# gameboy-macro.net
KiCad netlist of a schematic drawn in EAGLE
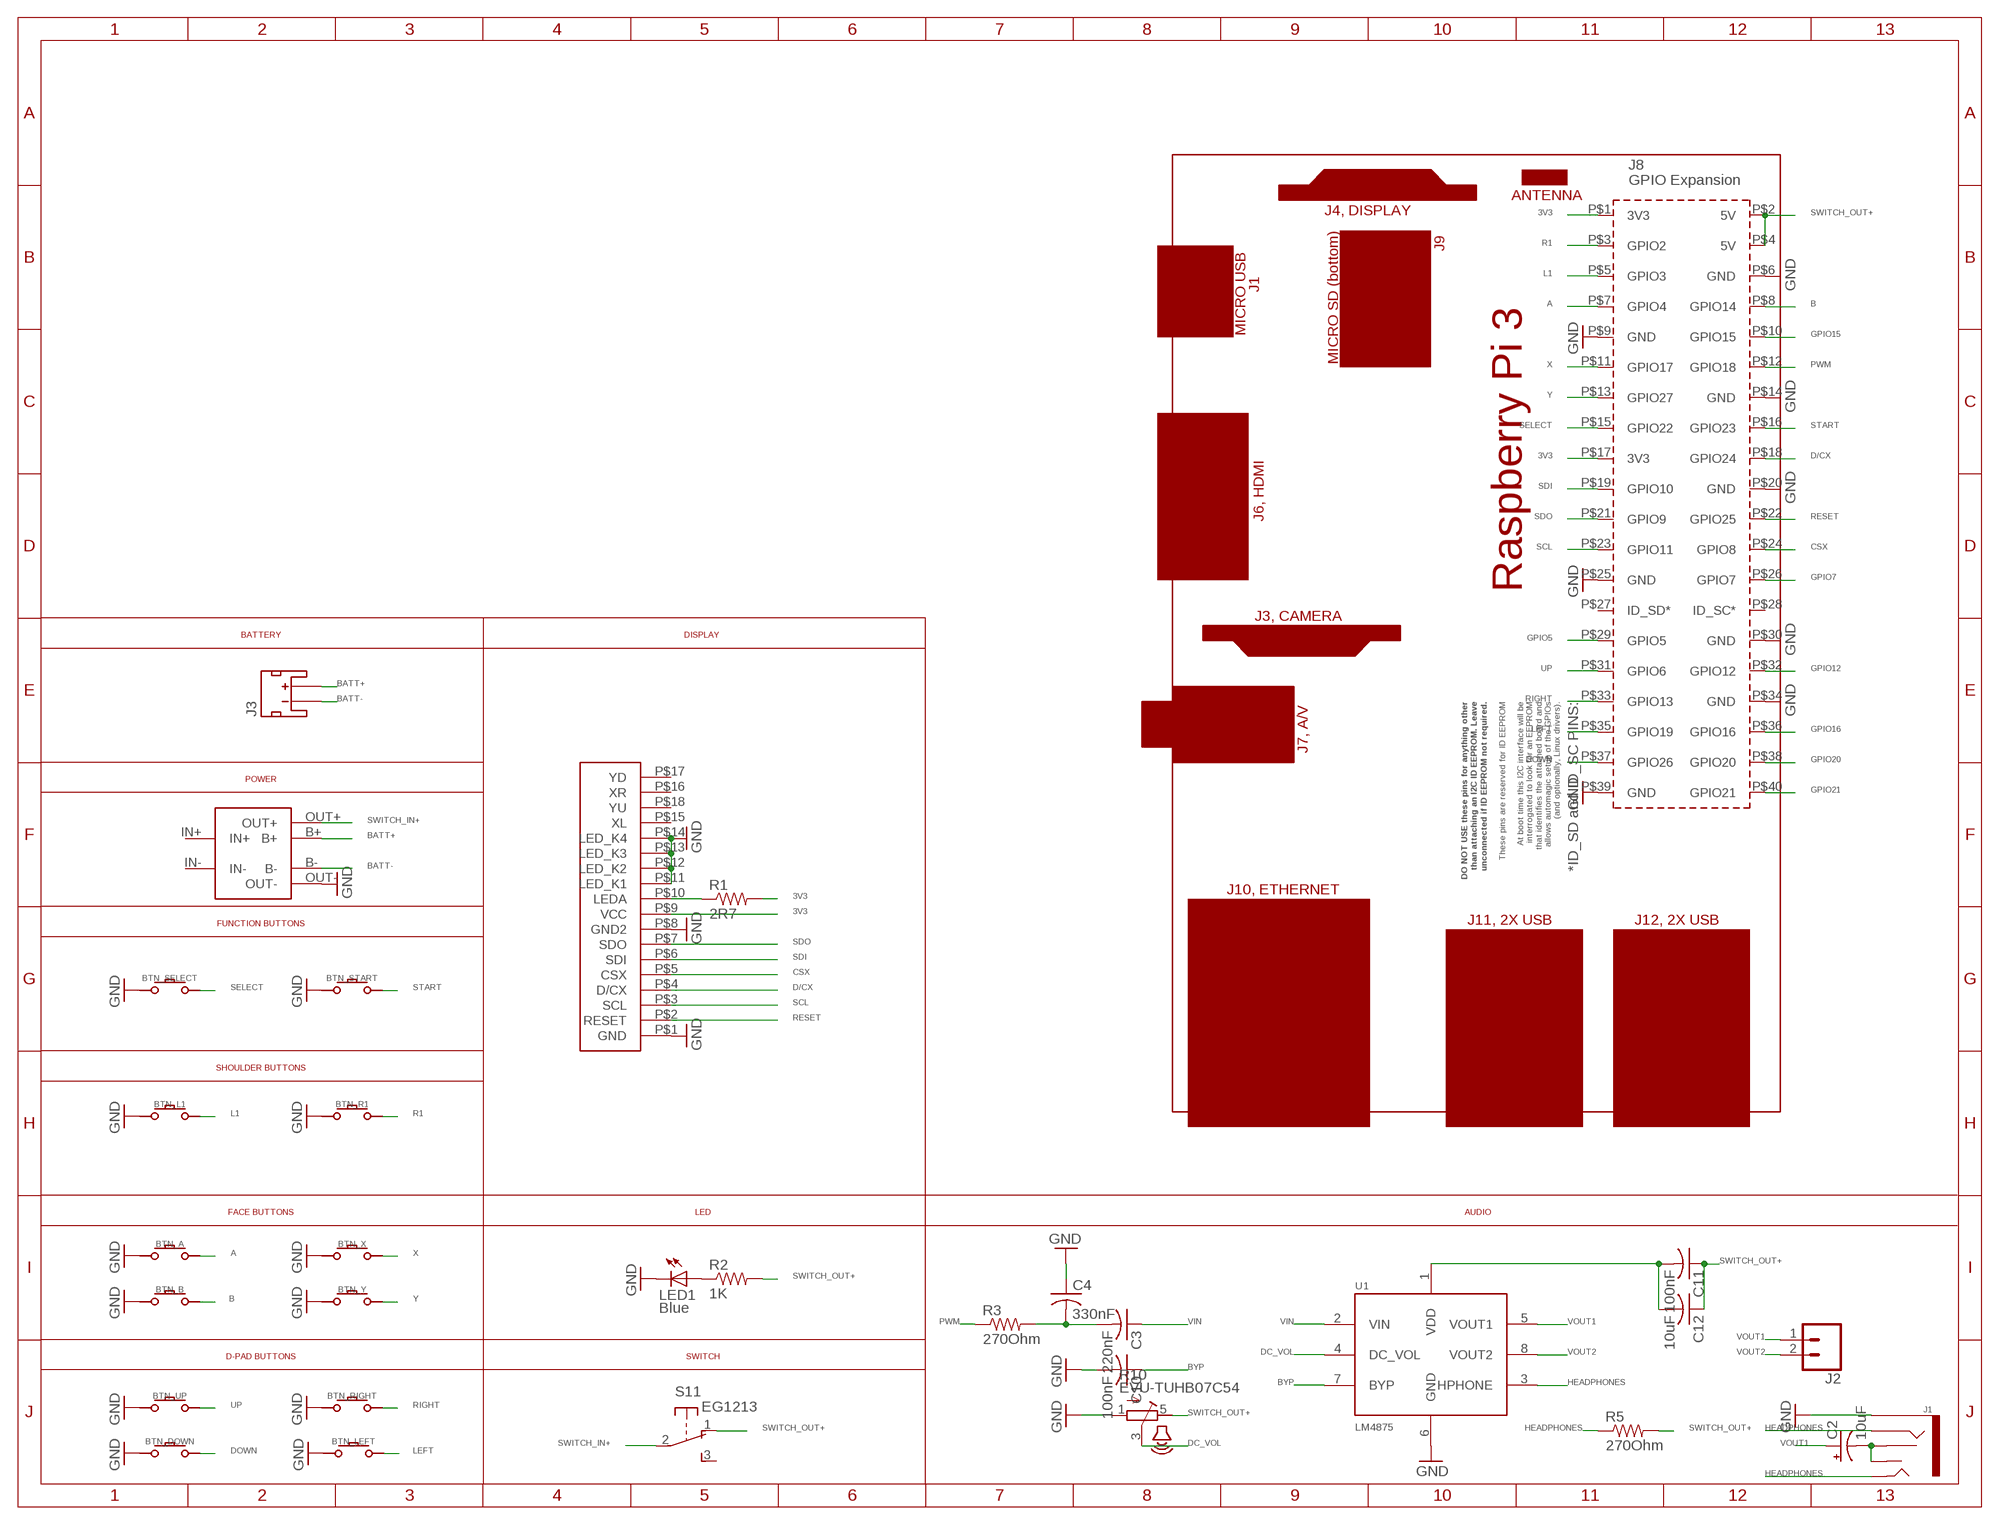
[diagram p0: schematic, sheet 1]

(export (version "E")
  (design (tool "Eeschema 10.0.6"))
  (components
    (comp (ref "BTN_A")
      (value "GAMEBOY-ZERO-BUTTON")
      (footprint "eagle-import:GAMEBOY-ZERO-BUTTON")
      (libsource (lib "eagle-import") (part "GAMEBOY-ZERO-BUTTON"))
    )
    (comp (ref "BTN_B")
      (value "GAMEBOY-ZERO-BUTTON")
      (footprint "eagle-import:GAMEBOY-ZERO-BUTTON")
      (libsource (lib "eagle-import") (part "GAMEBOY-ZERO-BUTTON"))
    )
    (comp (ref "BTN_DOWN")
      (value "GAMEBOY-ZERO-BUTTON")
      (footprint "eagle-import:GAMEBOY-ZERO-BUTTON")
      (libsource (lib "eagle-import") (part "GAMEBOY-ZERO-BUTTON"))
    )
    (comp (ref "BTN_L1")
      (value "GAMEBOY-ZERO-BUTTON")
      (footprint "eagle-import:GAMEBOY-ZERO-BUTTON")
      (libsource (lib "eagle-import") (part "GAMEBOY-ZERO-BUTTON"))
    )
    (comp (ref "BTN_LEFT")
      (value "GAMEBOY-ZERO-BUTTON")
      (footprint "eagle-import:GAMEBOY-ZERO-BUTTON")
      (libsource (lib "eagle-import") (part "GAMEBOY-ZERO-BUTTON"))
    )
    (comp (ref "BTN_R1")
      (value "GAMEBOY-ZERO-BUTTON")
      (footprint "eagle-import:GAMEBOY-ZERO-BUTTON")
      (libsource (lib "eagle-import") (part "GAMEBOY-ZERO-BUTTON"))
    )
    (comp (ref "BTN_RIGHT")
      (value "GAMEBOY-ZERO-BUTTON")
      (footprint "eagle-import:GAMEBOY-ZERO-BUTTON")
      (libsource (lib "eagle-import") (part "GAMEBOY-ZERO-BUTTON"))
    )
    (comp (ref "BTN_SELECT")
      (value "GAMEBOY-ZERO-BUTTON")
      (footprint "eagle-import:GAMEBOY-ZERO-BUTTON")
      (libsource (lib "eagle-import") (part "GAMEBOY-ZERO-BUTTON"))
    )
    (comp (ref "BTN_START")
      (value "GAMEBOY-ZERO-BUTTON")
      (footprint "eagle-import:GAMEBOY-ZERO-BUTTON")
      (libsource (lib "eagle-import") (part "GAMEBOY-ZERO-BUTTON"))
    )
    (comp (ref "BTN_UP")
      (value "GAMEBOY-ZERO-BUTTON")
      (footprint "eagle-import:GAMEBOY-ZERO-BUTTON")
      (libsource (lib "eagle-import") (part "GAMEBOY-ZERO-BUTTON"))
    )
    (comp (ref "BTN_X")
      (value "GAMEBOY-ZERO-BUTTON")
      (footprint "eagle-import:GAMEBOY-ZERO-BUTTON")
      (libsource (lib "eagle-import") (part "GAMEBOY-ZERO-BUTTON"))
    )
    (comp (ref "BTN_Y")
      (value "GAMEBOY-ZERO-BUTTON")
      (footprint "eagle-import:GAMEBOY-ZERO-BUTTON")
      (libsource (lib "eagle-import") (part "GAMEBOY-ZERO-BUTTON"))
    )
    (comp (ref "C2")
      (value "10uF")
      (footprint "eagle-import:EIA3216")
      (libsource (lib "eagle-import") (part "10UF-POLAR-EIA3216-16V-10%(TANT)"))
    )
    (comp (ref "C3")
      (value "220nF")
      (footprint "eagle-import:C0805")
      (libsource (lib "eagle-import") (part "C-USC0805"))
    )
    (comp (ref "C4")
      (value "330nF")
      (footprint "eagle-import:C0805")
      (libsource (lib "eagle-import") (part "C-USC0805"))
    )
    (comp (ref "C10")
      (value "100nF")
      (footprint "eagle-import:C0805")
      (libsource (lib "eagle-import") (part "C-USC0805"))
    )
    (comp (ref "C11")
      (value "100nF")
      (footprint "eagle-import:C0805")
      (libsource (lib "eagle-import") (part "C-USC0805"))
    )
    (comp (ref "C12")
      (value "10uF")
      (footprint "eagle-import:C0805")
      (libsource (lib "eagle-import") (part "C-USC0805"))
    )
    (comp (ref "ILI9341-TFT-2.8")
      (value "GAMEBOYZEROHANDHELDDISPLAYS-3.2")
      (footprint "eagle-import:GAMEBOYZEROHANDHELDDISPLAYS-3.2")
      (libsource (lib "eagle-import") (part "GAMEBOYZEROHANDHELDDISPLAYS-3.2"))
    )
    (comp (ref "J1")
      (value "AUDIO_JACK_3.5MM_PTH")
      (footprint "eagle-import:AUDIO-JACK")
      (libsource (lib "eagle-import") (part "AUDIO_JACK_3.5MM_PTH"))
    )
    (comp (ref "J2")
      (value "CONN_02")
      (footprint "eagle-import:1X02")
      (libsource (lib "eagle-import") (part "CONN_02"))
    )
    (comp (ref "J3")
      (value "JST_2MM_MALE")
      (footprint "eagle-import:JST-2-SMD")
      (libsource (lib "eagle-import") (part "JST_2MM_MALE"))
    )
    (comp (ref "LED1")
      (value "Blue")
      (footprint "eagle-import:CHIPLED_0805")
      (libsource (lib "eagle-import") (part "LEDCHIPLED_0805"))
    )
    (comp (ref "PCB1")
      (value "RPI3RPI3")
      (footprint "eagle-import:RPI3")
      (libsource (lib "eagle-import") (part "RPI3RPI3"))
    )
    (comp (ref "POWER1")
      (value "03962A")
      (footprint "eagle-import:03962A")
      (libsource (lib "eagle-import") (part "03962A"))
    )
    (comp (ref "R1")
      (value "2R7")
      (footprint "eagle-import:R0805")
      (libsource (lib "eagle-import") (part "R-US_R0805"))
    )
    (comp (ref "R2")
      (value "1K")
      (footprint "eagle-import:R0805")
      (libsource (lib "eagle-import") (part "R-US_R0805"))
    )
    (comp (ref "R3")
      (value "270Ohm")
      (footprint "eagle-import:R0805")
      (libsource (lib "eagle-import") (part "adafruit_420_R-US_R0805"))
    )
    (comp (ref "R5")
      (value "270Ohm")
      (footprint "eagle-import:R0805")
      (libsource (lib "eagle-import") (part "adafruit_420_R-US_R0805"))
    )
    (comp (ref "R10")
      (value "EVU-TUHB07C54")
      (footprint "eagle-import:VOLUME")
      (libsource (lib "eagle-import") (part "VOLUME"))
    )
    (comp (ref "S1")
      (value "EG1213")
      (footprint "eagle-import:EG1213")
      (libsource (lib "eagle-import") (part "EG1213"))
    )
    (comp (ref "U1")
      (value "LM4875")
      (footprint "eagle-import:SOIC8")
      (libsource (lib "eagle-import") (part "LM4875"))
    )
  )
  (nets
    (net (code "1") (name "/3V3") (class "Default")
      (node (ref "ILI9341-TFT-2.8") (pin "P$9") (pinfunction "VCC_P$9") (pintype "bidirectional"))
      (node (ref "PCB1") (pin "P$1") (pinfunction "3V3_P$1") (pintype "bidirectional"))
      (node (ref "PCB1") (pin "P$17") (pinfunction "3V3_P$17") (pintype "bidirectional"))
      (node (ref "R1") (pin "2") (pinfunction "2_2") (pintype "passive"))
    )
    (net (code "2") (name "/A") (class "Default")
      (node (ref "BTN_A") (pin "P$ACTIVE") (pinfunction "P$ACTIVE_P$ACTIVE") (pintype "bidirectional"))
      (node (ref "PCB1") (pin "P$7") (pinfunction "GPIO4_P$7") (pintype "bidirectional"))
    )
    (net (code "3") (name "/B") (class "Default")
      (node (ref "BTN_B") (pin "P$ACTIVE") (pinfunction "P$ACTIVE_P$ACTIVE") (pintype "bidirectional"))
      (node (ref "PCB1") (pin "P$8") (pinfunction "GPIO14_P$8") (pintype "bidirectional"))
    )
    (net (code "4") (name "/BATT+") (class "Default")
      (node (ref "J3") (pin "2") (pinfunction "+_2") (pintype "bidirectional"))
      (node (ref "POWER1") (pin "B+") (pinfunction "B+_B+") (pintype "bidirectional"))
    )
    (net (code "5") (name "/BATT-") (class "Default")
      (node (ref "J3") (pin "1") (pinfunction "-_1") (pintype "bidirectional"))
      (node (ref "POWER1") (pin "B-") (pinfunction "B-_B-") (pintype "bidirectional"))
    )
    (net (code "6") (name "/BYP") (class "Default")
      (node (ref "C10") (pin "1") (pinfunction "1_1") (pintype "passive"))
      (node (ref "U1") (pin "7") (pinfunction "BYP_7") (pintype "bidirectional"))
    )
    (net (code "7") (name "/CSX") (class "Default")
      (node (ref "ILI9341-TFT-2.8") (pin "P$5") (pinfunction "CSX_P$5") (pintype "bidirectional"))
      (node (ref "PCB1") (pin "P$24") (pinfunction "GPIO8_P$24") (pintype "bidirectional"))
    )
    (net (code "8") (name "/DC_VOL") (class "Default")
      (node (ref "R10") (pin "3") (pinfunction "S_3") (pintype "passive"))
      (node (ref "U1") (pin "4") (pinfunction "DC_VOL_4") (pintype "input"))
    )
    (net (code "9") (name "/DOWN") (class "Default")
      (node (ref "BTN_DOWN") (pin "P$ACTIVE") (pinfunction "P$ACTIVE_P$ACTIVE") (pintype "bidirectional"))
      (node (ref "PCB1") (pin "P$37") (pinfunction "GPIO26_P$37") (pintype "bidirectional"))
    )
    (net (code "10") (name "/D{slash}CX") (class "Default")
      (node (ref "ILI9341-TFT-2.8") (pin "P$4") (pinfunction "D/CX_P$4") (pintype "bidirectional"))
      (node (ref "PCB1") (pin "P$18") (pinfunction "GPIO24_P$18") (pintype "bidirectional"))
    )
    (net (code "11") (name "/GPIO5") (class "Default")
      (node (ref "PCB1") (pin "P$29") (pinfunction "GPIO5_P$29") (pintype "bidirectional"))
    )
    (net (code "12") (name "/GPIO7") (class "Default")
      (node (ref "PCB1") (pin "P$26") (pinfunction "GPIO7_P$26") (pintype "bidirectional"))
    )
    (net (code "13") (name "/GPIO12") (class "Default")
      (node (ref "PCB1") (pin "P$32") (pinfunction "GPIO12_P$32") (pintype "bidirectional"))
    )
    (net (code "14") (name "/GPIO15") (class "Default")
      (node (ref "PCB1") (pin "P$10") (pinfunction "GPIO15_P$10") (pintype "bidirectional"))
    )
    (net (code "15") (name "/GPIO16") (class "Default")
      (node (ref "PCB1") (pin "P$36") (pinfunction "GPIO16_P$36") (pintype "bidirectional"))
    )
    (net (code "16") (name "/GPIO20") (class "Default")
      (node (ref "PCB1") (pin "P$38") (pinfunction "GPIO20_P$38") (pintype "bidirectional"))
    )
    (net (code "17") (name "/GPIO21") (class "Default")
      (node (ref "PCB1") (pin "P$40") (pinfunction "GPIO21_P$40") (pintype "bidirectional"))
    )
    (net (code "18") (name "/HEADPHONES") (class "Default")
      (node (ref "J1") (pin "RING") (pinfunction "RING_RING") (pintype "bidirectional"))
      (node (ref "J1") (pin "TIP") (pinfunction "TIP_TIP") (pintype "bidirectional"))
      (node (ref "R5") (pin "1") (pinfunction "1_1") (pintype "passive"))
      (node (ref "U1") (pin "3") (pinfunction "HPHONE_3") (pintype "input"))
    )
    (net (code "19") (name "/L1") (class "Default")
      (node (ref "BTN_L1") (pin "P$ACTIVE") (pinfunction "P$ACTIVE_P$ACTIVE") (pintype "bidirectional"))
      (node (ref "PCB1") (pin "P$5") (pinfunction "GPIO3_P$5") (pintype "bidirectional"))
    )
    (net (code "20") (name "/LEFT") (class "Default")
      (node (ref "BTN_LEFT") (pin "P$ACTIVE") (pinfunction "P$ACTIVE_P$ACTIVE") (pintype "bidirectional"))
      (node (ref "PCB1") (pin "P$35") (pinfunction "GPIO19_P$35") (pintype "bidirectional"))
    )
    (net (code "21") (name "/PWM") (class "Default")
      (node (ref "PCB1") (pin "P$12") (pinfunction "GPIO18_P$12") (pintype "bidirectional"))
      (node (ref "R3") (pin "1") (pinfunction "1_1") (pintype "passive"))
    )
    (net (code "22") (name "/R1") (class "Default")
      (node (ref "BTN_R1") (pin "P$ACTIVE") (pinfunction "P$ACTIVE_P$ACTIVE") (pintype "bidirectional"))
      (node (ref "PCB1") (pin "P$3") (pinfunction "GPIO2_P$3") (pintype "bidirectional"))
    )
    (net (code "23") (name "/RESET") (class "Default")
      (node (ref "ILI9341-TFT-2.8") (pin "P$2") (pinfunction "RESET_P$2") (pintype "bidirectional"))
      (node (ref "PCB1") (pin "P$22") (pinfunction "GPIO25_P$22") (pintype "bidirectional"))
    )
    (net (code "24") (name "/RIGHT") (class "Default")
      (node (ref "BTN_RIGHT") (pin "P$ACTIVE") (pinfunction "P$ACTIVE_P$ACTIVE") (pintype "bidirectional"))
      (node (ref "PCB1") (pin "P$33") (pinfunction "GPIO13_P$33") (pintype "bidirectional"))
    )
    (net (code "25") (name "/SCL") (class "Default")
      (node (ref "ILI9341-TFT-2.8") (pin "P$3") (pinfunction "SCL_P$3") (pintype "bidirectional"))
      (node (ref "PCB1") (pin "P$23") (pinfunction "GPIO11_P$23") (pintype "bidirectional"))
    )
    (net (code "26") (name "/SDI") (class "Default")
      (node (ref "ILI9341-TFT-2.8") (pin "P$6") (pinfunction "SDI_P$6") (pintype "bidirectional"))
      (node (ref "PCB1") (pin "P$19") (pinfunction "GPIO10_P$19") (pintype "bidirectional"))
    )
    (net (code "27") (name "/SDO") (class "Default")
      (node (ref "ILI9341-TFT-2.8") (pin "P$7") (pinfunction "SDO_P$7") (pintype "bidirectional"))
      (node (ref "PCB1") (pin "P$21") (pinfunction "GPIO9_P$21") (pintype "bidirectional"))
    )
    (net (code "28") (name "/SELECT") (class "Default")
      (node (ref "BTN_SELECT") (pin "P$ACTIVE") (pinfunction "P$ACTIVE_P$ACTIVE") (pintype "bidirectional"))
      (node (ref "PCB1") (pin "P$15") (pinfunction "GPIO22_P$15") (pintype "bidirectional"))
    )
    (net (code "29") (name "/START") (class "Default")
      (node (ref "BTN_START") (pin "P$ACTIVE") (pinfunction "P$ACTIVE_P$ACTIVE") (pintype "bidirectional"))
      (node (ref "PCB1") (pin "P$16") (pinfunction "GPIO23_P$16") (pintype "bidirectional"))
    )
    (net (code "30") (name "/SWITCH_IN+") (class "Default")
      (node (ref "POWER1") (pin "OUT+") (pinfunction "OUT+_OUT+") (pintype "bidirectional"))
      (node (ref "S1") (pin "2") (pinfunction "P_2") (pintype "passive"))
    )
    (net (code "31") (name "/SWITCH_OUT+") (class "Default")
      (node (ref "C11") (pin "1") (pinfunction "1_1") (pintype "passive"))
      (node (ref "C12") (pin "1") (pinfunction "1_1") (pintype "passive"))
      (node (ref "PCB1") (pin "P$2") (pinfunction "5V_P$2") (pintype "bidirectional"))
      (node (ref "PCB1") (pin "P$4") (pinfunction "5V_P$4") (pintype "bidirectional"))
      (node (ref "R10") (pin "5") (pinfunction "E_5") (pintype "passive"))
      (node (ref "R2") (pin "2") (pinfunction "2_2") (pintype "passive"))
      (node (ref "R5") (pin "2") (pinfunction "2_2") (pintype "passive"))
      (node (ref "S1") (pin "1") (pinfunction "O_1") (pintype "passive"))
    )
    (net (code "32") (name "/UP") (class "Default")
      (node (ref "BTN_UP") (pin "P$ACTIVE") (pinfunction "P$ACTIVE_P$ACTIVE") (pintype "bidirectional"))
      (node (ref "PCB1") (pin "P$31") (pinfunction "GPIO6_P$31") (pintype "bidirectional"))
    )
    (net (code "33") (name "/VIN") (class "Default")
      (node (ref "C3") (pin "1") (pinfunction "1_1") (pintype "passive"))
      (node (ref "U1") (pin "2") (pinfunction "VIN_2") (pintype "input"))
    )
    (net (code "34") (name "/VOUT1") (class "Default")
      (node (ref "C2") (pin "+") (pinfunction "+_+") (pintype "passive"))
      (node (ref "J2") (pin "1") (pinfunction "1_1") (pintype "passive"))
      (node (ref "U1") (pin "5") (pinfunction "VOUT1_5") (pintype "output"))
    )
    (net (code "35") (name "/VOUT2") (class "Default")
      (node (ref "J2") (pin "2") (pinfunction "2_2") (pintype "passive"))
      (node (ref "U1") (pin "8") (pinfunction "VOUT2_8") (pintype "output"))
    )
    (net (code "36") (name "/X") (class "Default")
      (node (ref "BTN_X") (pin "P$ACTIVE") (pinfunction "P$ACTIVE_P$ACTIVE") (pintype "bidirectional"))
      (node (ref "PCB1") (pin "P$11") (pinfunction "GPIO17_P$11") (pintype "bidirectional"))
    )
    (net (code "37") (name "/Y") (class "Default")
      (node (ref "BTN_Y") (pin "P$ACTIVE") (pinfunction "P$ACTIVE_P$ACTIVE") (pintype "bidirectional"))
      (node (ref "PCB1") (pin "P$13") (pinfunction "GPIO27_P$13") (pintype "bidirectional"))
    )
    (net (code "38") (name "GND") (class "Default")
      (node (ref "BTN_A") (pin "P$GND") (pinfunction "P$GND_P$GND") (pintype "bidirectional"))
      (node (ref "BTN_B") (pin "P$GND") (pinfunction "P$GND_P$GND") (pintype "bidirectional"))
      (node (ref "BTN_DOWN") (pin "P$GND") (pinfunction "P$GND_P$GND") (pintype "bidirectional"))
      (node (ref "BTN_L1") (pin "P$GND") (pinfunction "P$GND_P$GND") (pintype "bidirectional"))
      (node (ref "BTN_LEFT") (pin "P$GND") (pinfunction "P$GND_P$GND") (pintype "bidirectional"))
      (node (ref "BTN_R1") (pin "P$GND") (pinfunction "P$GND_P$GND") (pintype "bidirectional"))
      (node (ref "BTN_RIGHT") (pin "P$GND") (pinfunction "P$GND_P$GND") (pintype "bidirectional"))
      (node (ref "BTN_SELECT") (pin "P$GND") (pinfunction "P$GND_P$GND") (pintype "bidirectional"))
      (node (ref "BTN_START") (pin "P$GND") (pinfunction "P$GND_P$GND") (pintype "bidirectional"))
      (node (ref "BTN_UP") (pin "P$GND") (pinfunction "P$GND_P$GND") (pintype "bidirectional"))
      (node (ref "BTN_X") (pin "P$GND") (pinfunction "P$GND_P$GND") (pintype "bidirectional"))
      (node (ref "BTN_Y") (pin "P$GND") (pinfunction "P$GND_P$GND") (pintype "bidirectional"))
      (node (ref "C10") (pin "2") (pinfunction "2_2") (pintype "passive"))
      (node (ref "C4") (pin "1") (pinfunction "1_1") (pintype "passive"))
      (node (ref "ILI9341-TFT-2.8") (pin "P$1") (pinfunction "GND_P$1") (pintype "bidirectional"))
      (node (ref "ILI9341-TFT-2.8") (pin "P$11") (pinfunction "LED_K1_P$11") (pintype "bidirectional"))
      (node (ref "ILI9341-TFT-2.8") (pin "P$12") (pinfunction "LED_K2_P$12") (pintype "bidirectional"))
      (node (ref "ILI9341-TFT-2.8") (pin "P$13") (pinfunction "LED_K3_P$13") (pintype "bidirectional"))
      (node (ref "ILI9341-TFT-2.8") (pin "P$14") (pinfunction "LED_K4_P$14") (pintype "bidirectional"))
      (node (ref "ILI9341-TFT-2.8") (pin "P$8") (pinfunction "GND2_P$8") (pintype "bidirectional"))
      (node (ref "J1") (pin "SLEEVE") (pinfunction "SLEEVE_SLEEVE") (pintype "bidirectional"))
      (node (ref "LED1") (pin "C") (pinfunction "C_C") (pintype "passive"))
      (node (ref "PCB1") (pin "P$14") (pinfunction "GND_P$14") (pintype "bidirectional"))
      (node (ref "PCB1") (pin "P$20") (pinfunction "GND_P$20") (pintype "bidirectional"))
      (node (ref "PCB1") (pin "P$25") (pinfunction "GND_P$25") (pintype "bidirectional"))
      (node (ref "PCB1") (pin "P$30") (pinfunction "GND_P$30") (pintype "bidirectional"))
      (node (ref "PCB1") (pin "P$34") (pinfunction "GND_P$34") (pintype "bidirectional"))
      (node (ref "PCB1") (pin "P$39") (pinfunction "GND_P$39") (pintype "bidirectional"))
      (node (ref "PCB1") (pin "P$6") (pinfunction "GND_P$6") (pintype "bidirectional"))
      (node (ref "PCB1") (pin "P$9") (pinfunction "GND_P$9") (pintype "bidirectional"))
      (node (ref "POWER1") (pin "OUT-") (pinfunction "OUT-_OUT-") (pintype "bidirectional"))
      (node (ref "R10") (pin "1") (pinfunction "A_1") (pintype "passive"))
      (node (ref "U1") (pin "6") (pinfunction "GND_6") (pintype "power_in"))
    )
    (net (code "39") (name "Net-(C2-Pad-)") (class "Default")
      (node (ref "C2") (pin "-") (pinfunction "-_-") (pintype "passive"))
      (node (ref "J1") (pin "RSH") (pinfunction "RSH_RSH") (pintype "bidirectional"))
      (node (ref "J1") (pin "TSH") (pinfunction "TSH_TSH") (pintype "bidirectional"))
    )
    (net (code "40") (name "Net-(C3-Pad2)") (class "Default")
      (node (ref "C3") (pin "2") (pinfunction "2_2") (pintype "passive"))
      (node (ref "C4") (pin "2") (pinfunction "2_2") (pintype "passive"))
      (node (ref "R3") (pin "2") (pinfunction "2_2") (pintype "passive"))
    )
    (net (code "41") (name "Net-(ILI9341-TFT-2.8-LEDA)") (class "Default")
      (node (ref "ILI9341-TFT-2.8") (pin "P$10") (pinfunction "LEDA_P$10") (pintype "bidirectional"))
      (node (ref "R1") (pin "1") (pinfunction "1_1") (pintype "passive"))
    )
    (net (code "42") (name "Net-(LED1-PadA)") (class "Default")
      (node (ref "LED1") (pin "A") (pinfunction "A_A") (pintype "passive"))
      (node (ref "R2") (pin "1") (pinfunction "1_1") (pintype "passive"))
    )
    (net (code "43") (name "Net-(U1-VDD)") (class "Default")
      (node (ref "C11") (pin "2") (pinfunction "2_2") (pintype "passive"))
      (node (ref "C12") (pin "2") (pinfunction "2_2") (pintype "passive"))
      (node (ref "U1") (pin "1") (pinfunction "VDD_1") (pintype "power_in"))
    )
    (net (code "44") (name "unconnected-(ILI9341-TFT-2.8-XL-PadP$15)") (class "Default")
      (node (ref "ILI9341-TFT-2.8") (pin "P$15") (pinfunction "XL_P$15") (pintype "bidirectional"))
    )
    (net (code "45") (name "unconnected-(ILI9341-TFT-2.8-XR-PadP$16)") (class "Default")
      (node (ref "ILI9341-TFT-2.8") (pin "P$16") (pinfunction "XR_P$16") (pintype "bidirectional"))
    )
    (net (code "46") (name "unconnected-(ILI9341-TFT-2.8-YD-PadP$17)") (class "Default")
      (node (ref "ILI9341-TFT-2.8") (pin "P$17") (pinfunction "YD_P$17") (pintype "bidirectional"))
    )
    (net (code "47") (name "unconnected-(ILI9341-TFT-2.8-YU-PadP$18)") (class "Default")
      (node (ref "ILI9341-TFT-2.8") (pin "P$18") (pinfunction "YU_P$18") (pintype "bidirectional"))
    )
    (net (code "48") (name "unconnected-(J3-PAD1-PadNC1)") (class "Default")
      (node (ref "J3") (pin "NC1") (pinfunction "PAD1_NC1") (pintype "bidirectional"))
    )
    (net (code "49") (name "unconnected-(J3-PAD2-PadNC2)") (class "Default")
      (node (ref "J3") (pin "NC2") (pinfunction "PAD2_NC2") (pintype "bidirectional"))
    )
    (net (code "50") (name "unconnected-(PCB1-ID_SC*-PadP$28)") (class "Default")
      (node (ref "PCB1") (pin "P$28") (pinfunction "ID_SC*_P$28") (pintype "bidirectional"))
    )
    (net (code "51") (name "unconnected-(PCB1-ID_SD*-PadP$27)") (class "Default")
      (node (ref "PCB1") (pin "P$27") (pinfunction "ID_SD*_P$27") (pintype "bidirectional"))
    )
    (net (code "52") (name "unconnected-(POWER1-PadIN+)") (class "Default")
      (node (ref "POWER1") (pin "IN+") (pinfunction "IN+_IN+") (pintype "bidirectional"))
    )
    (net (code "53") (name "unconnected-(POWER1-PadIN-)") (class "Default")
      (node (ref "POWER1") (pin "IN-") (pinfunction "IN-_IN-") (pintype "bidirectional"))
    )
    (net (code "54") (name "unconnected-(S1A-S-Pad3)") (class "Default")
      (node (ref "S1") (pin "3") (pinfunction "S_3") (pintype "passive"))
    )
  )
)
